# usbasp_mini.net
KiCad netlist of a schematic drawn in EAGLE
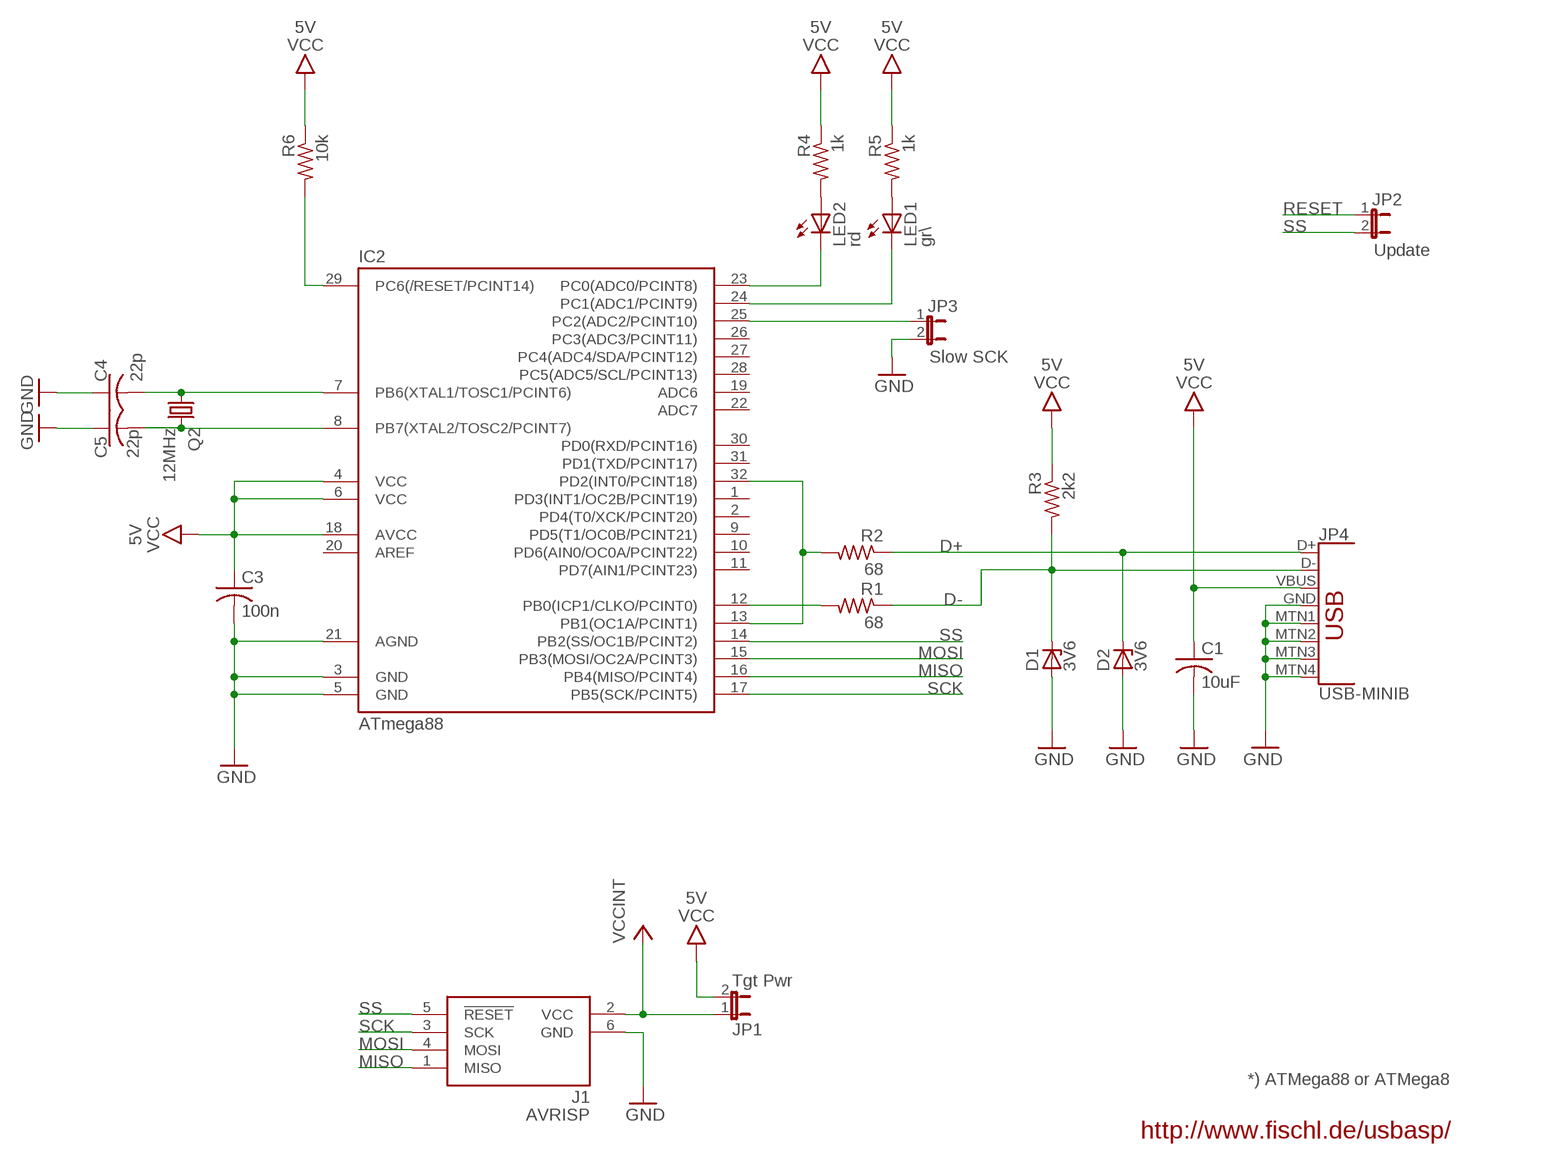
[diagram p0: schematic, sheet 1]

(export (version "E")
  (design (tool "Eeschema 10.0.6"))
  (components
    (comp (ref "C1")
      (value "10uF")
      (footprint "eagle-import:1206")
      (libsource (lib "eagle-import") (part "C-1206"))
    )
    (comp (ref "C3")
      (value "100n")
      (footprint "eagle-import:0603")
      (libsource (lib "eagle-import") (part "C-0603"))
    )
    (comp (ref "C4")
      (value "22p")
      (footprint "eagle-import:0603")
      (libsource (lib "eagle-import") (part "C-0603"))
    )
    (comp (ref "C5")
      (value "22p")
      (footprint "eagle-import:0603")
      (libsource (lib "eagle-import") (part "C-0603"))
    )
    (comp (ref "D1")
      (value "3V6")
      (footprint "eagle-import:SMB")
      (libsource (lib "eagle-import") (part "ZENER-DIODESMB"))
    )
    (comp (ref "D2")
      (value "3V6")
      (footprint "eagle-import:SMB")
      (libsource (lib "eagle-import") (part "ZENER-DIODESMB"))
    )
    (comp (ref "IC2")
      (value "ATmega88")
      (footprint "eagle-import:TQFP32-08")
      (libsource (lib "eagle-import") (part "MEGA48/88/168-AU"))
    )
    (comp (ref "J1")
      (value "AVRISP")
      (footprint "eagle-import:CON6P2R")
      (libsource (lib "eagle-import") (part "AVRISP6_COMPACT"))
    )
    (comp (ref "JP1")
      (value "Tgt Pwr")
      (footprint "eagle-import:JP1")
      (libsource (lib "eagle-import") (part "JP1E"))
    )
    (comp (ref "JP2")
      (value "Update")
      (footprint "eagle-import:JP1")
      (libsource (lib "eagle-import") (part "JP1E"))
    )
    (comp (ref "JP3")
      (value "Slow SCK")
      (footprint "eagle-import:JP1")
      (libsource (lib "eagle-import") (part "JP1E"))
    )
    (comp (ref "JP4")
      (value "USB-MINIB")
      (footprint "eagle-import:USB-MINIB")
      (libsource (lib "eagle-import") (part "USB-MINIB"))
    )
    (comp (ref "LED1")
      (value "gr\\")
      (footprint "eagle-import:CHIPLED_0603")
      (libsource (lib "eagle-import") (part "LEDCHIPLED_0603"))
    )
    (comp (ref "LED2")
      (value "rd")
      (footprint "eagle-import:CHIPLED_0603")
      (libsource (lib "eagle-import") (part "LEDCHIPLED_0603"))
    )
    (comp (ref "Q2")
      (value "12MHz")
      (footprint "eagle-import:NDK_2PAD_5X3")
      (libsource (lib "eagle-import") (part "CRYSTALNDK5X3"))
    )
    (comp (ref "R1")
      (value "68")
      (footprint "eagle-import:0603")
      (libsource (lib "eagle-import") (part "R0603"))
    )
    (comp (ref "R2")
      (value "68")
      (footprint "eagle-import:0603")
      (libsource (lib "eagle-import") (part "R0603"))
    )
    (comp (ref "R3")
      (value "2k2")
      (footprint "eagle-import:0603")
      (libsource (lib "eagle-import") (part "R0603"))
    )
    (comp (ref "R4")
      (value "1k")
      (footprint "eagle-import:0603")
      (libsource (lib "eagle-import") (part "R0603"))
    )
    (comp (ref "R5")
      (value "1k")
      (footprint "eagle-import:0603")
      (libsource (lib "eagle-import") (part "R0603"))
    )
    (comp (ref "R6")
      (value "10k")
      (footprint "eagle-import:0603")
      (libsource (lib "eagle-import") (part "R0603"))
    )
  )
  (nets
    (net (code "1") (name "/D+") (class "Default")
      (node (ref "D2") (pin "C") (pinfunction "C_C") (pintype "passive"))
      (node (ref "JP4") (pin "D+") (pinfunction "D+_D+") (pintype "bidirectional"))
      (node (ref "R2") (pin "1") (pinfunction "1_1") (pintype "passive"))
    )
    (net (code "2") (name "/D-") (class "Default")
      (node (ref "D1") (pin "C") (pinfunction "C_C") (pintype "passive"))
      (node (ref "JP4") (pin "D-") (pinfunction "D-_D-") (pintype "bidirectional"))
      (node (ref "R1") (pin "1") (pinfunction "1_1") (pintype "passive"))
      (node (ref "R3") (pin "2") (pinfunction "2_2") (pintype "passive"))
    )
    (net (code "3") (name "/MISO") (class "Default")
      (node (ref "IC2") (pin "16") (pinfunction "PB4(MISO/PCINT4)_16") (pintype "bidirectional"))
      (node (ref "J1") (pin "1") (pinfunction "MISO_1") (pintype "input"))
    )
    (net (code "4") (name "/MOSI") (class "Default")
      (node (ref "IC2") (pin "15") (pinfunction "PB3(MOSI/OC2A/PCINT3)_15") (pintype "bidirectional"))
      (node (ref "J1") (pin "4") (pinfunction "MOSI_4") (pintype "output"))
    )
    (net (code "5") (name "/RESET") (class "Default")
      (node (ref "IC2") (pin "29") (pinfunction "PC6(/RESET/PCINT14)_29") (pintype "bidirectional"))
      (node (ref "JP2") (pin "1") (pinfunction "1_1") (pintype "passive"))
      (node (ref "R6") (pin "2") (pinfunction "2_2") (pintype "passive"))
    )
    (net (code "6") (name "/SCK") (class "Default")
      (node (ref "IC2") (pin "17") (pinfunction "PB5(SCK/PCINT5)_17") (pintype "bidirectional"))
      (node (ref "J1") (pin "3") (pinfunction "SCK_3") (pintype "output"))
    )
    (net (code "7") (name "/SS") (class "Default")
      (node (ref "IC2") (pin "14") (pinfunction "PB2(SS/OC1B/PCINT2)_14") (pintype "bidirectional"))
      (node (ref "J1") (pin "5") (pinfunction "~{RESET}_5") (pintype "output"))
      (node (ref "JP2") (pin "2") (pinfunction "2_2") (pintype "passive"))
    )
    (net (code "8") (name "5V") (class "Default")
      (node (ref "C1") (pin "1") (pinfunction "+_1") (pintype "passive"))
      (node (ref "C3") (pin "1") (pinfunction "+_1") (pintype "passive"))
      (node (ref "IC2") (pin "18") (pinfunction "AVCC_18") (pintype "passive"))
      (node (ref "IC2") (pin "4") (pinfunction "VCC_4") (pintype "power_in"))
      (node (ref "IC2") (pin "6") (pinfunction "VCC_6") (pintype "power_in"))
      (node (ref "JP1") (pin "2") (pinfunction "2_2") (pintype "passive"))
      (node (ref "JP4") (pin "VBUS") (pinfunction "VBUS_VBUS") (pintype "bidirectional"))
      (node (ref "R3") (pin "1") (pinfunction "1_1") (pintype "passive"))
      (node (ref "R4") (pin "1") (pinfunction "1_1") (pintype "passive"))
      (node (ref "R5") (pin "1") (pinfunction "1_1") (pintype "passive"))
      (node (ref "R6") (pin "1") (pinfunction "1_1") (pintype "passive"))
    )
    (net (code "9") (name "GND") (class "Default")
      (node (ref "C1") (pin "2") (pinfunction "-_2") (pintype "passive"))
      (node (ref "C3") (pin "2") (pinfunction "-_2") (pintype "passive"))
      (node (ref "C4") (pin "1") (pinfunction "+_1") (pintype "passive"))
      (node (ref "C5") (pin "1") (pinfunction "+_1") (pintype "passive"))
      (node (ref "D1") (pin "A") (pinfunction "A_A") (pintype "passive"))
      (node (ref "D2") (pin "A") (pinfunction "A_A") (pintype "passive"))
      (node (ref "IC2") (pin "21") (pinfunction "AGND_21") (pintype "power_in"))
      (node (ref "IC2") (pin "3") (pinfunction "GND_3") (pintype "power_in"))
      (node (ref "IC2") (pin "5") (pinfunction "GND_5") (pintype "power_in"))
      (node (ref "J1") (pin "6") (pinfunction "GND_6") (pintype "power_in"))
      (node (ref "JP3") (pin "2") (pinfunction "2_2") (pintype "passive"))
      (node (ref "JP4") (pin "GND") (pinfunction "GND_GND") (pintype "bidirectional"))
      (node (ref "JP4") (pin "MTN1") (pinfunction "SHIELD1_MTN1") (pintype "bidirectional"))
      (node (ref "JP4") (pin "MTN2") (pinfunction "SHIELD2_MTN2") (pintype "bidirectional"))
      (node (ref "JP4") (pin "MTN3") (pinfunction "SHIELD3_MTN3") (pintype "bidirectional"))
      (node (ref "JP4") (pin "MTN4") (pinfunction "SHIELD4_MTN4") (pintype "bidirectional"))
    )
    (net (code "10") (name "Net-(C4--)") (class "Default")
      (node (ref "C4") (pin "2") (pinfunction "-_2") (pintype "passive"))
      (node (ref "IC2") (pin "7") (pinfunction "PB6(XTAL1/TOSC1/PCINT6)_7") (pintype "bidirectional"))
      (node (ref "Q2") (pin "P$1") (pinfunction "1_P$1") (pintype "passive"))
    )
    (net (code "11") (name "Net-(C5--)") (class "Default")
      (node (ref "C5") (pin "2") (pinfunction "-_2") (pintype "passive"))
      (node (ref "IC2") (pin "8") (pinfunction "PB7(XTAL2/TOSC2/PCINT7)_8") (pintype "bidirectional"))
      (node (ref "Q2") (pin "P$2") (pinfunction "2_P$2") (pintype "passive"))
    )
    (net (code "12") (name "Net-(IC2-PB0(ICP1{slash}CLKO{slash}PCINT0))") (class "Default")
      (node (ref "IC2") (pin "12") (pinfunction "PB0(ICP1/CLKO/PCINT0)_12") (pintype "bidirectional"))
      (node (ref "R1") (pin "2") (pinfunction "2_2") (pintype "passive"))
    )
    (net (code "13") (name "Net-(IC2-PB1(OC1A{slash}PCINT1))") (class "Default")
      (node (ref "IC2") (pin "13") (pinfunction "PB1(OC1A/PCINT1)_13") (pintype "bidirectional"))
      (node (ref "IC2") (pin "32") (pinfunction "PD2(INT0/PCINT18)_32") (pintype "bidirectional"))
      (node (ref "R2") (pin "2") (pinfunction "2_2") (pintype "passive"))
    )
    (net (code "14") (name "Net-(IC2-PC0(ADC0{slash}PCINT8))") (class "Default")
      (node (ref "IC2") (pin "23") (pinfunction "PC0(ADC0/PCINT8)_23") (pintype "bidirectional"))
      (node (ref "LED2") (pin "C") (pinfunction "C_C") (pintype "passive"))
    )
    (net (code "15") (name "Net-(IC2-PC1(ADC1{slash}PCINT9))") (class "Default")
      (node (ref "IC2") (pin "24") (pinfunction "PC1(ADC1/PCINT9)_24") (pintype "bidirectional"))
      (node (ref "LED1") (pin "C") (pinfunction "C_C") (pintype "passive"))
    )
    (net (code "16") (name "Net-(IC2-PC2(ADC2{slash}PCINT10))") (class "Default")
      (node (ref "IC2") (pin "25") (pinfunction "PC2(ADC2/PCINT10)_25") (pintype "bidirectional"))
      (node (ref "JP3") (pin "1") (pinfunction "1_1") (pintype "passive"))
    )
    (net (code "17") (name "Net-(LED1-PadA)") (class "Default")
      (node (ref "LED1") (pin "A") (pinfunction "A_A") (pintype "passive"))
      (node (ref "R5") (pin "2") (pinfunction "2_2") (pintype "passive"))
    )
    (net (code "18") (name "Net-(LED2-PadA)") (class "Default")
      (node (ref "LED2") (pin "A") (pinfunction "A_A") (pintype "passive"))
      (node (ref "R4") (pin "2") (pinfunction "2_2") (pintype "passive"))
    )
    (net (code "19") (name "VCCINT") (class "Default")
      (node (ref "J1") (pin "2") (pinfunction "VCC_2") (pintype "power_in"))
      (node (ref "JP1") (pin "1") (pinfunction "1_1") (pintype "passive"))
    )
    (net (code "20") (name "unconnected-(IC2-ADC6-Pad19)") (class "Default")
      (node (ref "IC2") (pin "19") (pinfunction "ADC6_19") (pintype "passive"))
    )
    (net (code "21") (name "unconnected-(IC2-ADC7-Pad22)") (class "Default")
      (node (ref "IC2") (pin "22") (pinfunction "ADC7_22") (pintype "passive"))
    )
    (net (code "22") (name "unconnected-(IC2-AREF-Pad20)") (class "Default")
      (node (ref "IC2") (pin "20") (pinfunction "AREF_20") (pintype "passive"))
    )
    (net (code "23") (name "unconnected-(IC2-PC3(ADC3{slash}PCINT11)-Pad26)") (class "Default")
      (node (ref "IC2") (pin "26") (pinfunction "PC3(ADC3/PCINT11)_26") (pintype "bidirectional"))
    )
    (net (code "24") (name "unconnected-(IC2-PC4(ADC4{slash}SDA{slash}PCINT12)-Pad27)") (class "Default")
      (node (ref "IC2") (pin "27") (pinfunction "PC4(ADC4/SDA/PCINT12)_27") (pintype "bidirectional"))
    )
    (net (code "25") (name "unconnected-(IC2-PC5(ADC5{slash}SCL{slash}PCINT13)-Pad28)") (class "Default")
      (node (ref "IC2") (pin "28") (pinfunction "PC5(ADC5/SCL/PCINT13)_28") (pintype "bidirectional"))
    )
    (net (code "26") (name "unconnected-(IC2-PD0(RXD{slash}PCINT16)-Pad30)") (class "Default")
      (node (ref "IC2") (pin "30") (pinfunction "PD0(RXD/PCINT16)_30") (pintype "bidirectional"))
    )
    (net (code "27") (name "unconnected-(IC2-PD1(TXD{slash}PCINT17)-Pad31)") (class "Default")
      (node (ref "IC2") (pin "31") (pinfunction "PD1(TXD/PCINT17)_31") (pintype "bidirectional"))
    )
    (net (code "28") (name "unconnected-(IC2-PD3(INT1{slash}OC2B{slash}PCINT19)-Pad1)") (class "Default")
      (node (ref "IC2") (pin "1") (pinfunction "PD3(INT1/OC2B/PCINT19)_1") (pintype "bidirectional"))
    )
    (net (code "29") (name "unconnected-(IC2-PD4(T0{slash}XCK{slash}PCINT20)-Pad2)") (class "Default")
      (node (ref "IC2") (pin "2") (pinfunction "PD4(T0/XCK/PCINT20)_2") (pintype "bidirectional"))
    )
    (net (code "30") (name "unconnected-(IC2-PD5(T1{slash}OC0B{slash}PCINT21)-Pad9)") (class "Default")
      (node (ref "IC2") (pin "9") (pinfunction "PD5(T1/OC0B/PCINT21)_9") (pintype "bidirectional"))
    )
    (net (code "31") (name "unconnected-(IC2-PD6(AIN0{slash}OC0A{slash}PCINT22)-Pad10)") (class "Default")
      (node (ref "IC2") (pin "10") (pinfunction "PD6(AIN0/OC0A/PCINT22)_10") (pintype "bidirectional"))
    )
    (net (code "32") (name "unconnected-(IC2-PD7(AIN1{slash}PCINT23)-Pad11)") (class "Default")
      (node (ref "IC2") (pin "11") (pinfunction "PD7(AIN1/PCINT23)_11") (pintype "bidirectional"))
    )
  )
)
